# MKRWAN1310V3_0.net
KiCad netlist of a schematic drawn in EAGLE
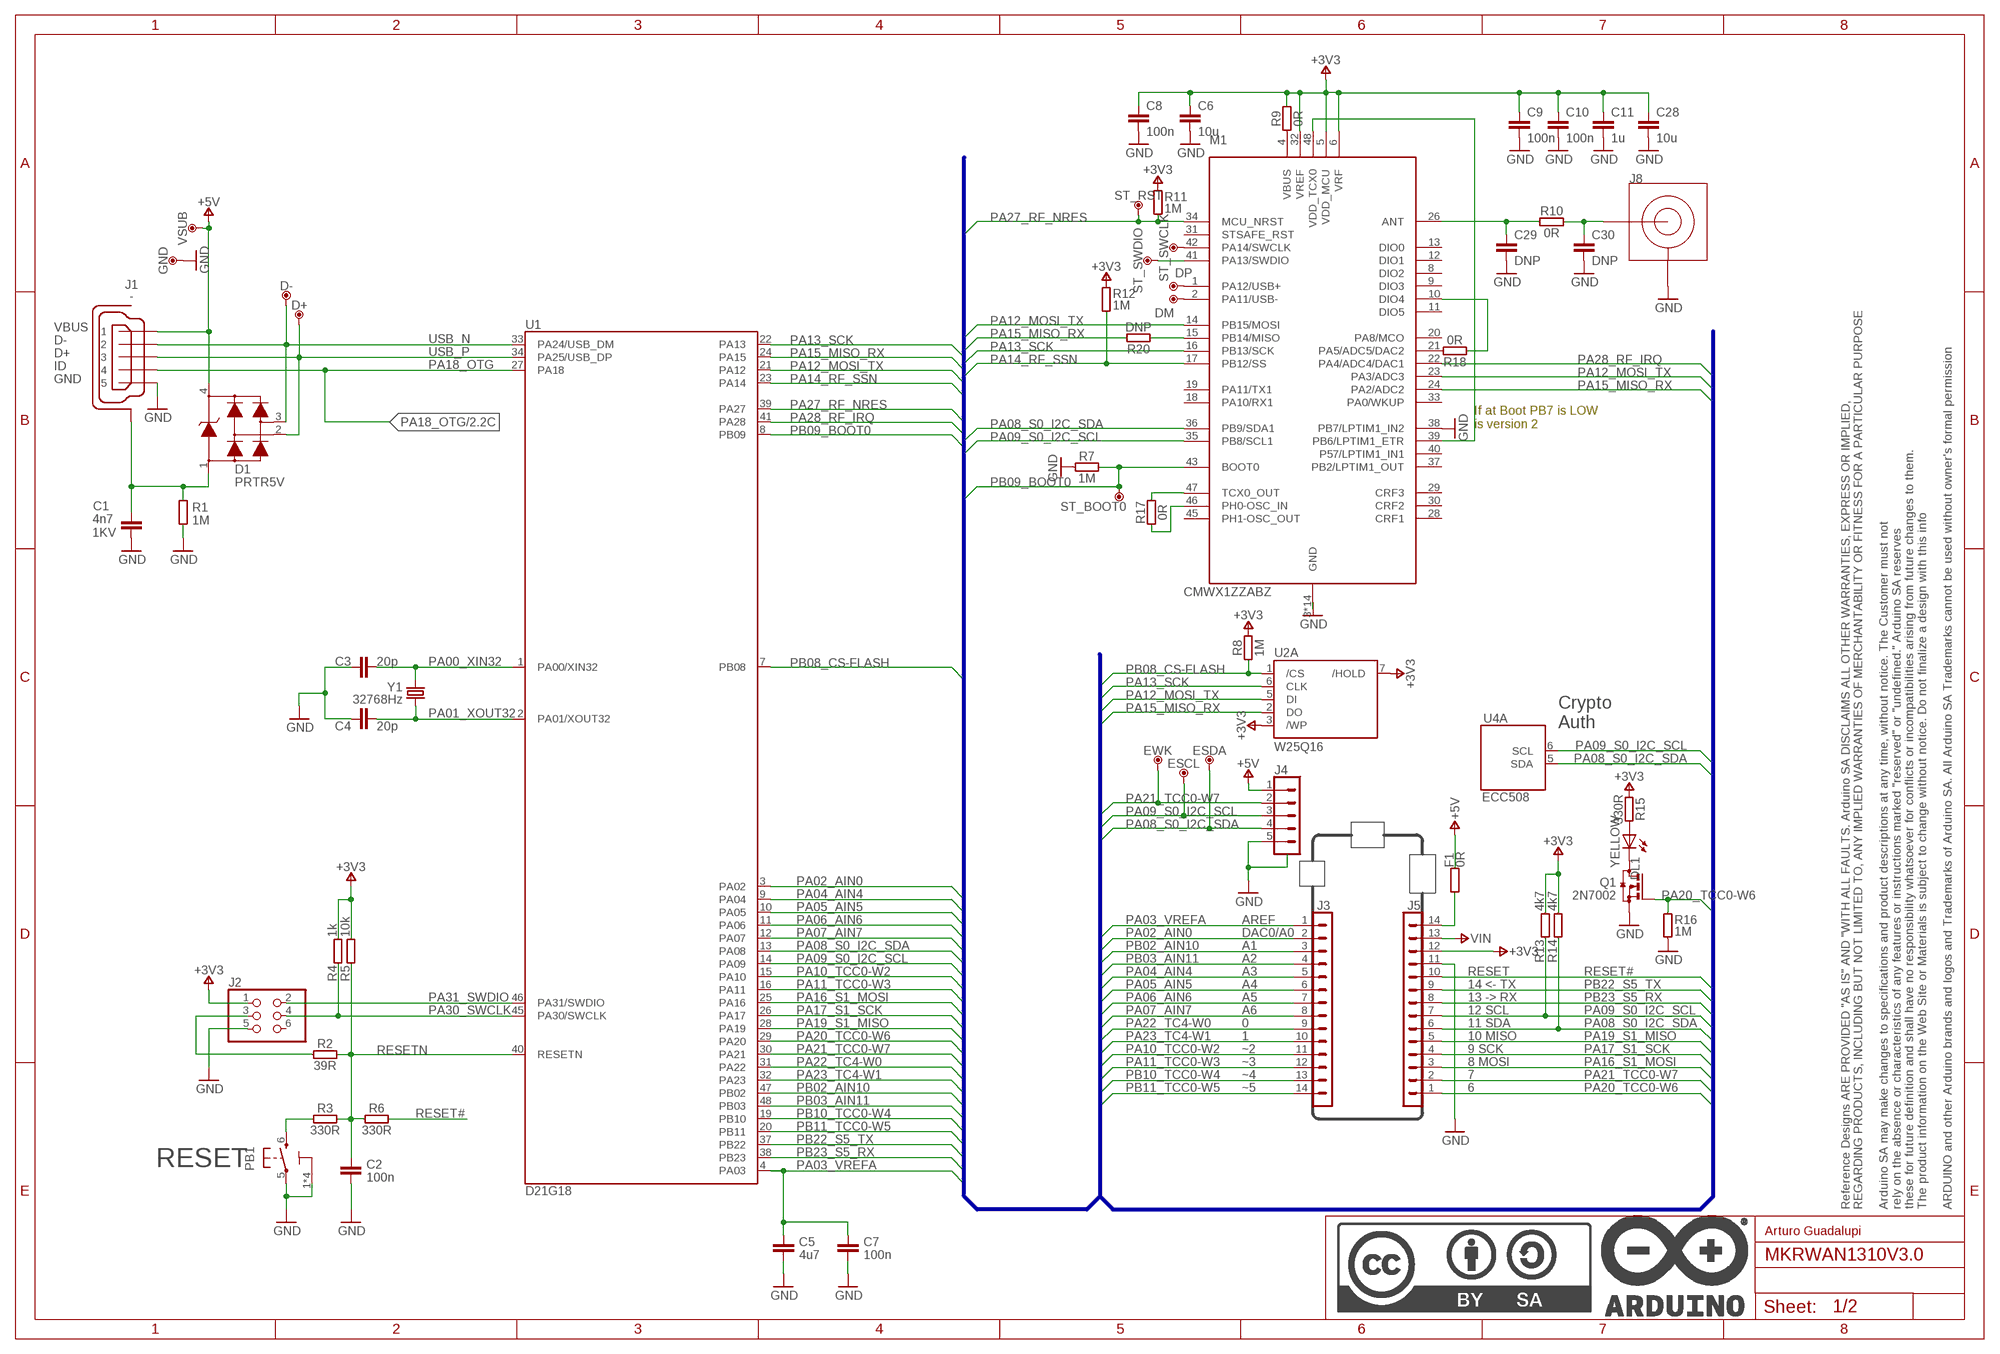
[diagram p0: schematic, sheet 1]
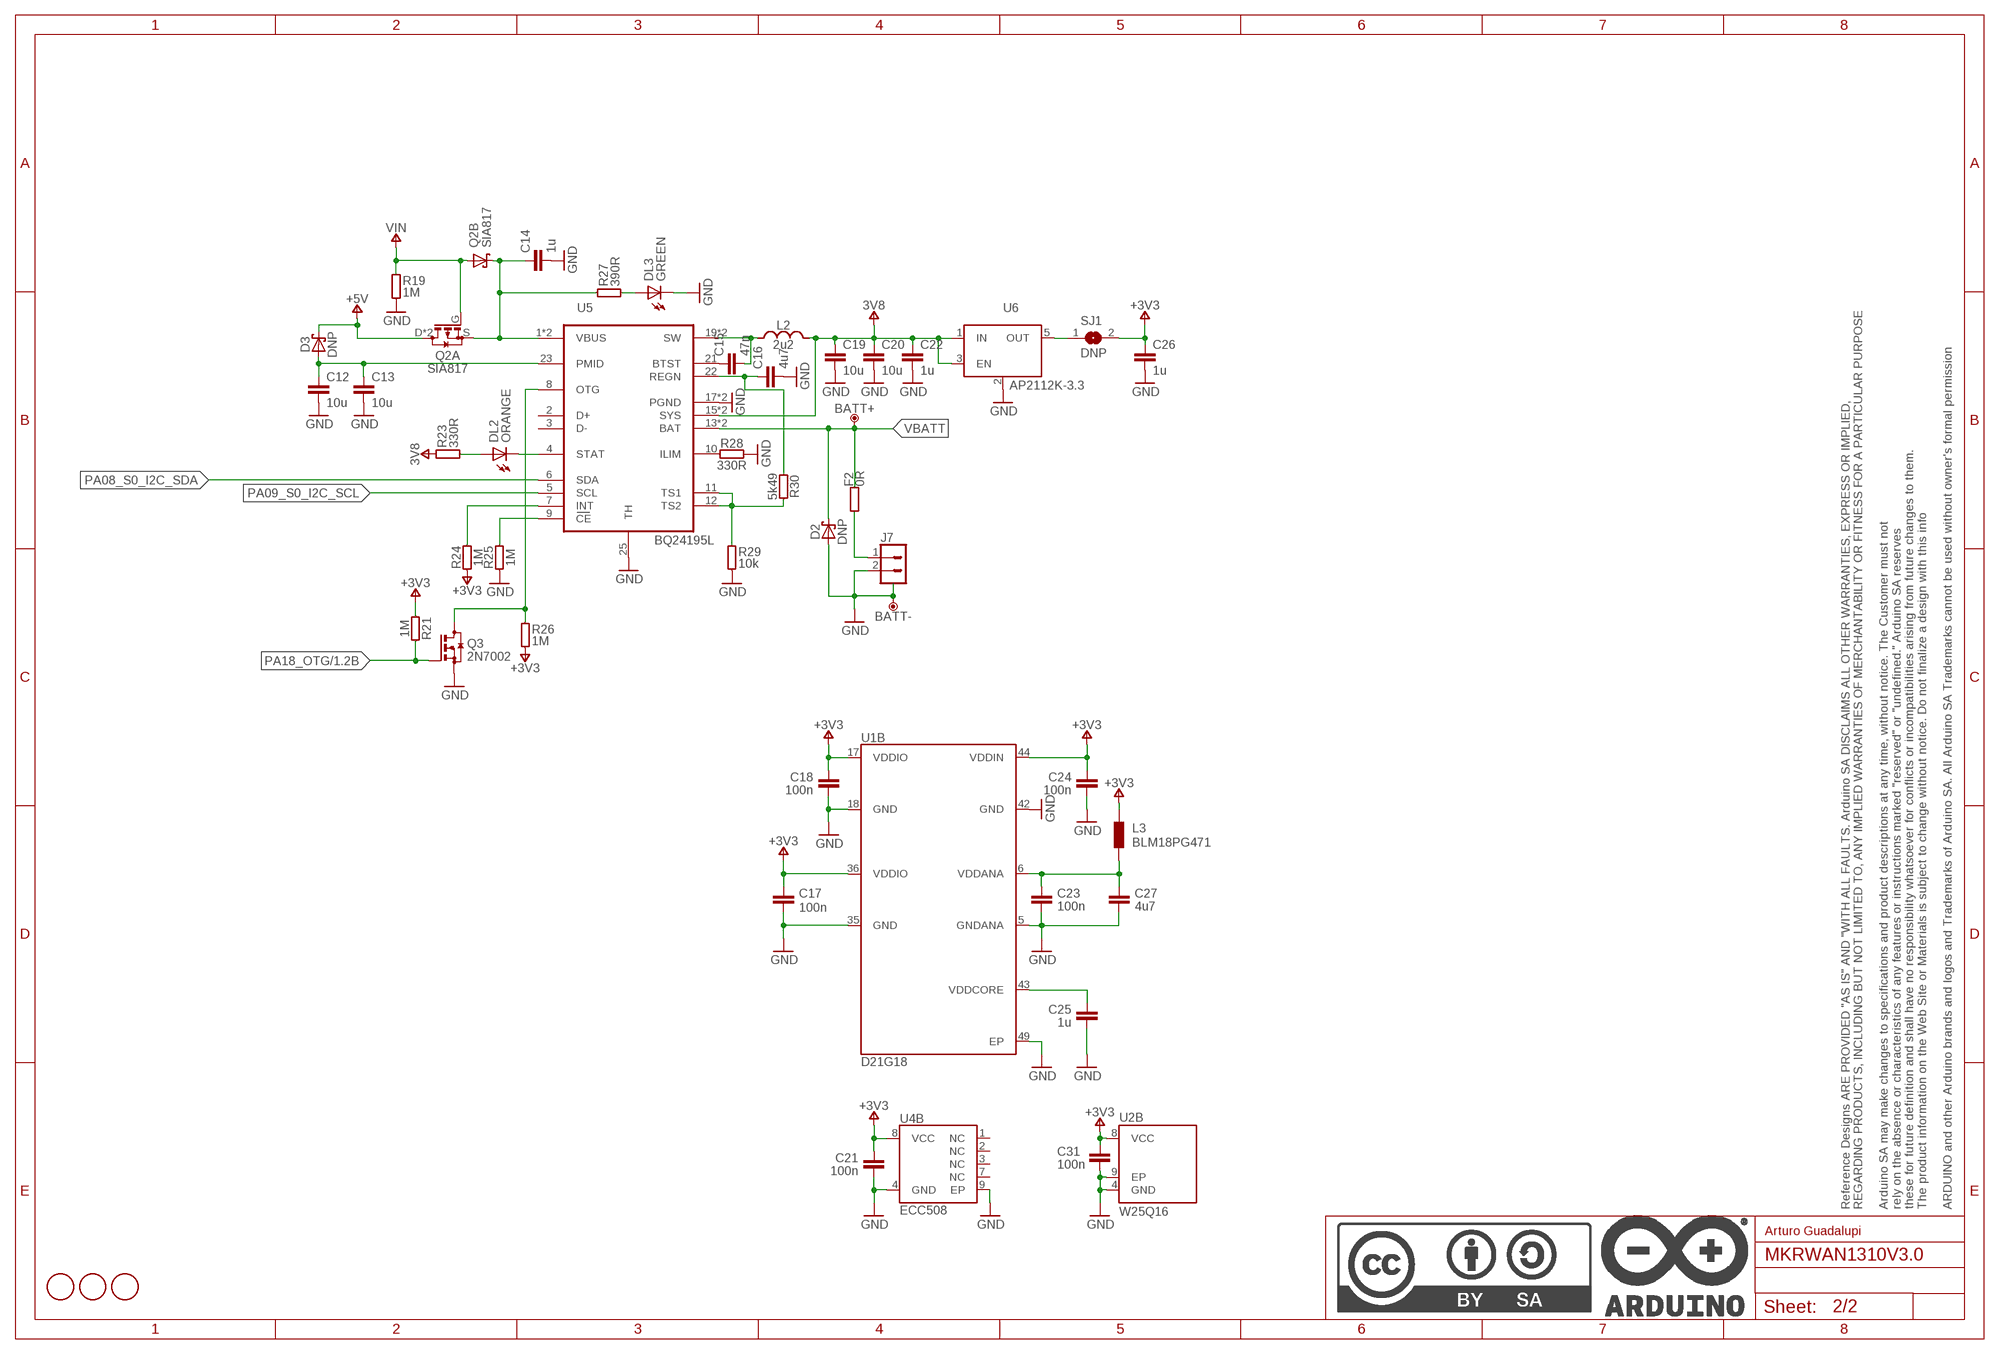
[diagram p1: schematic, sheet 2]

(export (version "E")
  (design (tool "Eeschema 10.0.6"))
  (components
    (comp (ref "C1")
      (value "4n7")
      (footprint "eagle-import:0805-R2013X50N")
      (fields (field (name "MANUFACTURER") "Kemet") (field (name "VOLTAGE") "1KV"))
      (libsource (lib "eagle-import") (part "C-08054.7NF"))
    )
    (comp (ref "C2")
      (value "100n")
      (footprint "eagle-import:0402-1005X55N")
      (fields (field (name "MANUFACTURER") "TDK"))
      (libsource (lib "eagle-import") (part "C-0402-100NF"))
    )
    (comp (ref "C3")
      (value "20p")
      (footprint "eagle-import:0402-1005X55N")
      (fields (field (name "MANUFACTURER") "Kemet"))
      (libsource (lib "eagle-import") (part "C-0402-20PF"))
    )
    (comp (ref "C4")
      (value "20p")
      (footprint "eagle-import:0402-1005X55N")
      (fields (field (name "MANUFACTURER") "Kemet"))
      (libsource (lib "eagle-import") (part "C-0402-20PF"))
    )
    (comp (ref "C5")
      (value "4u7")
      (footprint "eagle-import:0402-1005X55N")
      (fields (field (name "MANUFACTURER") "Murata"))
      (libsource (lib "eagle-import") (part "C-0402-4.7UF"))
    )
    (comp (ref "C6")
      (value "10u")
      (footprint "eagle-import:0603-1608X90N")
      (fields (field (name "MANUFACTURER") "Murata"))
      (libsource (lib "eagle-import") (part "C-0603-10UF"))
    )
    (comp (ref "C7")
      (value "100n")
      (footprint "eagle-import:0402-1005X55N")
      (fields (field (name "MANUFACTURER") "TDK"))
      (libsource (lib "eagle-import") (part "C-0402-100NF"))
    )
    (comp (ref "C8")
      (value "100n")
      (footprint "eagle-import:0402-1005X55N")
      (fields (field (name "MANUFACTURER") "TDK"))
      (libsource (lib "eagle-import") (part "C-0402-100NF"))
    )
    (comp (ref "C9")
      (value "100n")
      (footprint "eagle-import:0402-1005X55N")
      (fields (field (name "MANUFACTURER") "TDK"))
      (libsource (lib "eagle-import") (part "C-0402-100NF"))
    )
    (comp (ref "C10")
      (value "100n")
      (footprint "eagle-import:0402-1005X55N")
      (fields (field (name "MANUFACTURER") "TDK"))
      (libsource (lib "eagle-import") (part "C-0402-100NF"))
    )
    (comp (ref "C11")
      (value "1u")
      (footprint "eagle-import:0402-1005X55N")
      (fields (field (name "MANUFACTURER") "Murata"))
      (libsource (lib "eagle-import") (part "C-0402-1UF"))
    )
    (comp (ref "C28")
      (value "10u")
      (footprint "eagle-import:0603-1608X90N")
      (fields (field (name "MANUFACTURER") "Murata"))
      (libsource (lib "eagle-import") (part "C-0603-10UF"))
    )
    (comp (ref "C29")
      (value "DNP")
      (footprint "eagle-import:0402-1005X55N")
      (libsource (lib "eagle-import") (part "C-0402DNP"))
    )
    (comp (ref "C30")
      (value "DNP")
      (footprint "eagle-import:0402-1005X55N")
      (libsource (lib "eagle-import") (part "C-0402DNP"))
    )
    (comp (ref "D+")
      (value "DNP")
      (footprint "eagle-import:TP-1.00MM")
      (libsource (lib "eagle-import") (part "TPTP-1.00MM"))
    )
    (comp (ref "D-")
      (value "DNP")
      (footprint "eagle-import:TP-1.00MM")
      (libsource (lib "eagle-import") (part "TPTP-1.00MM"))
    )
    (comp (ref "D1")
      (value "PRTR5V")
      (footprint "eagle-import:SOT190P230X110-4N")
      (fields (field (name "MANUFACTURER") "NXP"))
      (libsource (lib "eagle-import") (part "PRTR5V0U2X,215"))
    )
    (comp (ref "DL1")
      (value "YELLOW")
      (footprint "eagle-import:LEDC1608X80N-AK")
      (fields (field (name "MANUFACTURER") "Avago"))
      (libsource (lib "eagle-import") (part "LED-0603-YELLOW"))
    )
    (comp (ref "DM")
      (value "DNP")
      (footprint "eagle-import:TP-1.27MM")
      (libsource (lib "eagle-import") (part "TPTP-1.27MM"))
    )
    (comp (ref "DP")
      (value "DNP")
      (footprint "eagle-import:TP-1.27MM")
      (libsource (lib "eagle-import") (part "TPTP-1.27MM"))
    )
    (comp (ref "ESCL")
      (value "DNP")
      (footprint "eagle-import:TP-1.00MM")
      (libsource (lib "eagle-import") (part "TPTP-1.00MM"))
    )
    (comp (ref "ESDA")
      (value "DNP")
      (footprint "eagle-import:TP-1.00MM")
      (libsource (lib "eagle-import") (part "TPTP-1.00MM"))
    )
    (comp (ref "EWK")
      (value "DNP")
      (footprint "eagle-import:TP-1.00MM")
      (libsource (lib "eagle-import") (part "TPTP-1.00MM"))
    )
    (comp (ref "F1")
      (value "0R")
      (footprint "eagle-import:C0603")
      (fields (field (name "MANUFACTURER") "Yageo"))
      (libsource (lib "eagle-import") (part "R-0603-0R"))
    )
    (comp (ref "FRAME1")
      (value "DNP")
      (footprint "eagle-import:FRAME")
      (libsource (lib "eagle-import") (part "A3-FRAME"))
    )
    (comp (ref "GND")
      (value "DNP")
      (footprint "eagle-import:TP-1.00MM")
      (libsource (lib "eagle-import") (part "TPTP-1.00MM"))
    )
    (comp (ref "J1")
      (value "-")
      (footprint "eagle-import:ZX62-AB-5PA")
      (fields (field (name "MANUFACTURER") "Hirose"))
      (libsource (lib "eagle-import") (part "USB-MICRO"))
    )
    (comp (ref "J2")
      (value "DNP")
      (footprint "eagle-import:2X3_SMT")
      (libsource (lib "eagle-import") (part "PINHD-2X03SMD-NH-DNP"))
    )
    (comp (ref "J3")
      (value "-")
      (footprint "eagle-import:1X14_SMD_TH")
      (fields (field (name "MANUFACTURER") "ELDECO"))
      (libsource (lib "eagle-import") (part "PINHD-1X14-SMTH-SMD-MALE/FEMALE"))
    )
    (comp (ref "J4")
      (value "-")
      (footprint "eagle-import:SM05B-SRSS-TB")
      (fields (field (name "MANUFACTURER") "JST"))
      (libsource (lib "eagle-import") (part "SM05B-SRSS-TB"))
    )
    (comp (ref "J5")
      (value "-")
      (footprint "eagle-import:1X14_SMD_TH")
      (fields (field (name "MANUFACTURER") "ELDECO"))
      (libsource (lib "eagle-import") (part "PINHD-1X14-SMTH-SMD-MALE/FEMALE"))
    )
    (comp (ref "J8")
      (value "-")
      (footprint "eagle-import:U.FL-R-SMT-1(60)")
      (fields (field (name "MANUFACTURER") "Hirose"))
      (libsource (lib "eagle-import") (part "UFL"))
    )
    (comp (ref "M1")
      (value "CMWX1ZZABZ")
      (footprint "eagle-import:CMWX1ZZABZ")
      (fields (field (name "MANUFACTURER") "Murata"))
      (libsource (lib "eagle-import") (part "CMWX1ZZABZ"))
    )
    (comp (ref "PB1")
      (value "PTS820")
      (footprint "eagle-import:C&K_PTS820_NO_HOLES")
      (fields (field (name "MANUFACTURER") "C&K"))
      (libsource (lib "eagle-import") (part "TACTILE1PTS820-NH"))
    )
    (comp (ref "Q1")
      (value "2N7002")
      (footprint "eagle-import:SOTFL50P160X78-3")
      (fields (field (name "MANUFACTURER") "Diodes Incorporated"))
      (libsource (lib "eagle-import") (part "2N7002T-SOT523"))
    )
    (comp (ref "R1")
      (value "1M")
      (footprint "eagle-import:0402-1005X55N")
      (fields (field (name "MANUFACTURER") "Yageo"))
      (libsource (lib "eagle-import") (part "R-0402-1M"))
    )
    (comp (ref "R2")
      (value "39R")
      (footprint "eagle-import:0402-1005X55N")
      (fields (field (name "MANUFACTURER") "Yageo "))
      (libsource (lib "eagle-import") (part "R-0402-39R"))
    )
    (comp (ref "R3")
      (value "330R")
      (footprint "eagle-import:0402-1005X55N")
      (fields (field (name "MANUFACTURER") "Yageo "))
      (libsource (lib "eagle-import") (part "R-0402-330R"))
    )
    (comp (ref "R4")
      (value "1k")
      (footprint "eagle-import:0402-1005X55N")
      (fields (field (name "MANUFACTURER") "Yageo"))
      (libsource (lib "eagle-import") (part "R-0402-1K"))
    )
    (comp (ref "R5")
      (value "10k")
      (footprint "eagle-import:0402-1005X55N")
      (fields (field (name "MANUFACTURER") "Yageo"))
      (libsource (lib "eagle-import") (part "R-0402-10K"))
    )
    (comp (ref "R6")
      (value "330R")
      (footprint "eagle-import:0402-1005X55N")
      (fields (field (name "MANUFACTURER") "Yageo "))
      (libsource (lib "eagle-import") (part "R-0402-330R"))
    )
    (comp (ref "R7")
      (value "1M")
      (footprint "eagle-import:0402-1005X55N")
      (fields (field (name "MANUFACTURER") "Yageo"))
      (libsource (lib "eagle-import") (part "R-0402-1M"))
    )
    (comp (ref "R8")
      (value "1M")
      (footprint "eagle-import:0402-1005X55N")
      (fields (field (name "MANUFACTURER") "Yageo"))
      (libsource (lib "eagle-import") (part "R-0402-1M"))
    )
    (comp (ref "R9")
      (value "0R")
      (footprint "eagle-import:0402-1005X55N")
      (fields (field (name "MANUFACTURER") "Yageo"))
      (libsource (lib "eagle-import") (part "R-0402-0R"))
    )
    (comp (ref "R10")
      (value "0R")
      (footprint "eagle-import:0402-1005X55N")
      (fields (field (name "MANUFACTURER") "Yageo"))
      (libsource (lib "eagle-import") (part "R-0402-0R"))
    )
    (comp (ref "R11")
      (value "1M")
      (footprint "eagle-import:0402-1005X55N")
      (fields (field (name "MANUFACTURER") "Yageo"))
      (libsource (lib "eagle-import") (part "R-0402-1M"))
    )
    (comp (ref "R12")
      (value "1M")
      (footprint "eagle-import:0402-1005X55N")
      (fields (field (name "MANUFACTURER") "Yageo"))
      (libsource (lib "eagle-import") (part "R-0402-1M"))
    )
    (comp (ref "R13")
      (value "4k7")
      (footprint "eagle-import:0402-1005X55N")
      (fields (field (name "MANUFACTURER") "Yageo "))
      (libsource (lib "eagle-import") (part "R-0402-4K7"))
    )
    (comp (ref "R14")
      (value "4k7")
      (footprint "eagle-import:0402-1005X55N")
      (fields (field (name "MANUFACTURER") "Yageo "))
      (libsource (lib "eagle-import") (part "R-0402-4K7"))
    )
    (comp (ref "R15")
      (value "330R")
      (footprint "eagle-import:0402-1005X55N")
      (fields (field (name "MANUFACTURER") "Yageo "))
      (libsource (lib "eagle-import") (part "R-0402-330R"))
    )
    (comp (ref "R16")
      (value "1M")
      (footprint "eagle-import:0402-1005X55N")
      (fields (field (name "MANUFACTURER") "Yageo"))
      (libsource (lib "eagle-import") (part "R-0402-1M"))
    )
    (comp (ref "R17")
      (value "0R")
      (footprint "eagle-import:0402-1005X55N")
      (fields (field (name "MANUFACTURER") "Yageo"))
      (libsource (lib "eagle-import") (part "R-0402-0R"))
    )
    (comp (ref "R18")
      (value "0R")
      (footprint "eagle-import:0402-1005X55N")
      (fields (field (name "MANUFACTURER") "Yageo"))
      (libsource (lib "eagle-import") (part "R-0402-0R"))
    )
    (comp (ref "R20")
      (value "DNP")
      (footprint "eagle-import:0402-1005X55N")
      (libsource (lib "eagle-import") (part "R-0402-DNP"))
    )
    (comp (ref "ST_BOOT0")
      (value "DNP")
      (footprint "eagle-import:TP-0.8MM")
      (libsource (lib "eagle-import") (part "TPTP-0.8MM"))
    )
    (comp (ref "ST_RST")
      (value "DNP")
      (footprint "eagle-import:TP-0.8MM")
      (libsource (lib "eagle-import") (part "TPTP-0.8MM"))
    )
    (comp (ref "ST_SWCLK")
      (value "DNP")
      (footprint "eagle-import:TP-0.8MM")
      (libsource (lib "eagle-import") (part "TPTP-0.8MM"))
    )
    (comp (ref "ST_SWDIO")
      (value "DNP")
      (footprint "eagle-import:TP-0.8MM")
      (libsource (lib "eagle-import") (part "TPTP-0.8MM"))
    )
    (comp (ref "U1")
      (value "D21G18")
      (footprint "eagle-import:QFN50P700X700X90-49XN-EPSQ515")
      (fields (field (name "MANUFACTURER") "Atmel"))
      (libsource (lib "eagle-import") (part "ATSAMD21G18A-48QFN"))
    )
    (comp (ref "U2")
      (value "W25Q16")
      (footprint "eagle-import:SON9P127_500X600X80L60X41T340X400N")
      (fields (field (name "MANUFACTURER") "Winbond"))
      (libsource (lib "eagle-import") (part "W25QZP16DV?IG"))
    )
    (comp (ref "U4")
      (value "ECC508")
      (footprint "eagle-import:SON50P300X200X60-9N-EP160X140")
      (fields (field (name "MANUFACTURER") "Atmel"))
      (libsource (lib "eagle-import") (part "ATECC508A-MAHDA-T8-UDFN"))
    )
    (comp (ref "VSUB")
      (value "DNP")
      (footprint "eagle-import:TP-1.00MM")
      (libsource (lib "eagle-import") (part "TPTP-1.00MM"))
    )
    (comp (ref "Y1")
      (value "32768Hz")
      (footprint "eagle-import:ABS07")
      (fields (field (name "MANUFACTURER") "Abracon LLC"))
      (libsource (lib "eagle-import") (part "32.768KHZ"))
    )
    (comp (ref "BATT+")
      (value "DNP")
      (footprint "eagle-import:TP-1.00MM")
      (libsource (lib "eagle-import") (part "TPTP-1.00MM"))
    )
    (comp (ref "BATT-")
      (value "DNP")
      (footprint "eagle-import:TP-1.00MM")
      (libsource (lib "eagle-import") (part "TPTP-1.00MM"))
    )
    (comp (ref "C12")
      (value "10u")
      (footprint "eagle-import:0603-1608X90N")
      (fields (field (name "MANUFACTURER") "Murata"))
      (libsource (lib "eagle-import") (part "C-0603-10UF"))
    )
    (comp (ref "C13")
      (value "10u")
      (footprint "eagle-import:0603-1608X90N")
      (fields (field (name "MANUFACTURER") "Murata"))
      (libsource (lib "eagle-import") (part "C-0603-10UF"))
    )
    (comp (ref "C14")
      (value "1u")
      (footprint "eagle-import:0402-1005X55N")
      (fields (field (name "MANUFACTURER") "Murata"))
      (libsource (lib "eagle-import") (part "C-0402-1UF"))
    )
    (comp (ref "C15")
      (value "47n")
      (footprint "eagle-import:0402-1005X55N")
      (fields (field (name "MANUFACTURER") "Murata"))
      (libsource (lib "eagle-import") (part "C-0402-47N"))
    )
    (comp (ref "C16")
      (value "4u7")
      (footprint "eagle-import:0402-1005X55N")
      (fields (field (name "MANUFACTURER") "Murata"))
      (libsource (lib "eagle-import") (part "C-0402-4.7UF"))
    )
    (comp (ref "C17")
      (value "100n")
      (footprint "eagle-import:0402-1005X55N")
      (fields (field (name "MANUFACTURER") "TDK"))
      (libsource (lib "eagle-import") (part "C-0402-100NF"))
    )
    (comp (ref "C18")
      (value "100n")
      (footprint "eagle-import:0402-1005X55N")
      (fields (field (name "MANUFACTURER") "TDK"))
      (libsource (lib "eagle-import") (part "C-0402-100NF"))
    )
    (comp (ref "C19")
      (value "10u")
      (footprint "eagle-import:0603-1608X90N")
      (fields (field (name "MANUFACTURER") "Murata"))
      (libsource (lib "eagle-import") (part "C-0603-10UF"))
    )
    (comp (ref "C20")
      (value "10u")
      (footprint "eagle-import:0603-1608X90N")
      (fields (field (name "MANUFACTURER") "Murata"))
      (libsource (lib "eagle-import") (part "C-0603-10UF"))
    )
    (comp (ref "C21")
      (value "100n")
      (footprint "eagle-import:0402-1005X55N")
      (fields (field (name "MANUFACTURER") "TDK"))
      (libsource (lib "eagle-import") (part "C-0402-100NF"))
    )
    (comp (ref "C22")
      (value "1u")
      (footprint "eagle-import:0402-1005X55N")
      (fields (field (name "MANUFACTURER") "Murata"))
      (libsource (lib "eagle-import") (part "C-0402-1UF"))
    )
    (comp (ref "C23")
      (value "100n")
      (footprint "eagle-import:0402-1005X55N")
      (fields (field (name "MANUFACTURER") "TDK"))
      (libsource (lib "eagle-import") (part "C-0402-100NF"))
    )
    (comp (ref "C24")
      (value "100n")
      (footprint "eagle-import:0402-1005X55N")
      (fields (field (name "MANUFACTURER") "TDK"))
      (libsource (lib "eagle-import") (part "C-0402-100NF"))
    )
    (comp (ref "C25")
      (value "1u")
      (footprint "eagle-import:0402-1005X55N")
      (fields (field (name "MANUFACTURER") "Murata"))
      (libsource (lib "eagle-import") (part "C-0402-1UF"))
    )
    (comp (ref "C26")
      (value "1u")
      (footprint "eagle-import:0402-1005X55N")
      (fields (field (name "MANUFACTURER") "Murata"))
      (libsource (lib "eagle-import") (part "C-0402-1UF"))
    )
    (comp (ref "C27")
      (value "4u7")
      (footprint "eagle-import:0603-1608X90N")
      (fields (field (name "MANUFACTURER") "Murata"))
      (libsource (lib "eagle-import") (part "C-0603-4.7UF"))
    )
    (comp (ref "C31")
      (value "100n")
      (footprint "eagle-import:0402-1005X55N")
      (fields (field (name "MANUFACTURER") "TDK"))
      (libsource (lib "eagle-import") (part "C-0402-100NF"))
    )
    (comp (ref "D2")
      (value "DNP")
      (footprint "eagle-import:SODFL3517X110N")
      (libsource (lib "eagle-import") (part "PMEG6020AELRX-DNP"))
    )
    (comp (ref "D3")
      (value "DNP")
      (footprint "eagle-import:SODFL3517X110N")
      (libsource (lib "eagle-import") (part "PMEG6020AELRX-DNP"))
    )
    (comp (ref "DL2")
      (value "ORANGE")
      (footprint "eagle-import:LEDC1608X80N-AK")
      (fields (field (name "MANUFACTURER") "Avago "))
      (libsource (lib "eagle-import") (part "LED-0603-ORANGE"))
    )
    (comp (ref "DL3")
      (value "GREEN")
      (footprint "eagle-import:LEDC1608X80N-AK")
      (fields (field (name "MANUFACTURER") "Avago "))
      (libsource (lib "eagle-import") (part "LED-0603-GREEN"))
    )
    (comp (ref "F2")
      (value "0R")
      (footprint "eagle-import:C0603")
      (fields (field (name "MANUFACTURER") "Yageo"))
      (libsource (lib "eagle-import") (part "R-0603-0R"))
    )
    (comp (ref "FD1")
      (value "DNP")
      (footprint "eagle-import:FD-1-1.5")
      (libsource (lib "eagle-import") (part "FIDUCIAL-1.5MM"))
    )
    (comp (ref "FD2")
      (value "DNP")
      (footprint "eagle-import:FD-1-1.5")
      (libsource (lib "eagle-import") (part "FIDUCIAL-1.5MM"))
    )
    (comp (ref "FD3")
      (value "DNP")
      (footprint "eagle-import:FD-1-1.5")
      (libsource (lib "eagle-import") (part "FIDUCIAL-1.5MM"))
    )
    (comp (ref "FRAME2")
      (value "DNP")
      (footprint "eagle-import:FRAME")
      (libsource (lib "eagle-import") (part "A3-FRAME"))
    )
    (comp (ref "J7")
      (value "-")
      (footprint "eagle-import:JST-S2B-PH-SM4-TB")
      (fields (field (name "MANUFACTURER") "JST "))
      (libsource (lib "eagle-import") (part "BATTERY"))
    )
    (comp (ref "L2")
      (value "2u2")
      (footprint "eagle-import:SRP4020")
      (fields (field (name "MANUFACTURER") "Bourns"))
      (libsource (lib "eagle-import") (part "LSRP"))
    )
    (comp (ref "L3")
      (value "BLM18PG471")
      (footprint "eagle-import:0603-1608X90N")
      (fields (field (name "MANUFACTURER") "Murata"))
      (libsource (lib "eagle-import") (part "FERRITE0603-470R"))
    )
    (comp (ref "Q2")
      (value "SIA817")
      (footprint "eagle-import:SON65P205X205X75-8N-MWSD")
      (fields (field (name "MANUFACTURER") "Vishay "))
      (libsource (lib "eagle-import") (part "SIA817EDJ"))
    )
    (comp (ref "Q3")
      (value "2N7002")
      (footprint "eagle-import:SOTFL50P160X78-3")
      (fields (field (name "MANUFACTURER") "Diodes Incorporated"))
      (libsource (lib "eagle-import") (part "2N7002T-SOT523"))
    )
    (comp (ref "R19")
      (value "1M")
      (footprint "eagle-import:0402-1005X55N")
      (fields (field (name "MANUFACTURER") "Yageo"))
      (libsource (lib "eagle-import") (part "R-0402-1M"))
    )
    (comp (ref "R21")
      (value "1M")
      (footprint "eagle-import:0402-1005X55N")
      (fields (field (name "MANUFACTURER") "Yageo"))
      (libsource (lib "eagle-import") (part "R-0402-1M"))
    )
    (comp (ref "R23")
      (value "330R")
      (footprint "eagle-import:0402-1005X55N")
      (fields (field (name "MANUFACTURER") "Yageo "))
      (libsource (lib "eagle-import") (part "R-0402-330R"))
    )
    (comp (ref "R24")
      (value "1M")
      (footprint "eagle-import:0402-1005X55N")
      (fields (field (name "MANUFACTURER") "Yageo"))
      (libsource (lib "eagle-import") (part "R-0402-1M"))
    )
    (comp (ref "R25")
      (value "1M")
      (footprint "eagle-import:0402-1005X55N")
      (fields (field (name "MANUFACTURER") "Yageo"))
      (libsource (lib "eagle-import") (part "R-0402-1M"))
    )
    (comp (ref "R26")
      (value "1M")
      (footprint "eagle-import:0402-1005X55N")
      (fields (field (name "MANUFACTURER") "Yageo"))
      (libsource (lib "eagle-import") (part "R-0402-1M"))
    )
    (comp (ref "R27")
      (value "390R")
      (footprint "eagle-import:0402-1005X55N")
      (fields (field (name "MANUFACTURER") "Yageo"))
      (libsource (lib "eagle-import") (part "R-0402-390R"))
    )
    (comp (ref "R28")
      (value "330R")
      (footprint "eagle-import:0402-1005X55N")
      (fields (field (name "MANUFACTURER") "Yageo "))
      (libsource (lib "eagle-import") (part "R-0402-330R"))
    )
    (comp (ref "R29")
      (value "10k")
      (footprint "eagle-import:0402-1005X55N")
      (fields (field (name "MANUFACTURER") "Yageo"))
      (libsource (lib "eagle-import") (part "R-0402-10K"))
    )
    (comp (ref "R30")
      (value "5k49")
      (footprint "eagle-import:0402-1005X55N")
      (fields (field (name "MANUFACTURER") "Yageo"))
      (libsource (lib "eagle-import") (part "R-0402-5K49"))
    )
    (comp (ref "SJ1")
      (value "DNP")
      (footprint "eagle-import:SJ")
      (libsource (lib "eagle-import") (part "SJ"))
    )
    (comp (ref "U5")
      (value "BQ24195L")
      (footprint "eagle-import:QFN24")
      (fields (field (name "MANUFACTURER") " Texas Instruments "))
      (libsource (lib "eagle-import") (part "BQ24195QFN-24"))
    )
    (comp (ref "U6")
      (value "AP2112K-3.3")
      (footprint "eagle-import:SOT25")
      (fields (field (name "MANUFACTURER") "Diodes Inc"))
      (libsource (lib "eagle-import") (part "AP2112K-3.3"))
    )
  )
  (nets
    (net (code "1") (name "+3V3") (class "Default")
      (node (ref "C10") (pin "1") (pinfunction "1_1") (pintype "passive"))
      (node (ref "C11") (pin "1") (pinfunction "1_1") (pintype "passive"))
      (node (ref "C17") (pin "1") (pinfunction "1_1") (pintype "passive"))
      (node (ref "C18") (pin "1") (pinfunction "1_1") (pintype "passive"))
      (node (ref "C21") (pin "1") (pinfunction "1_1") (pintype "passive"))
      (node (ref "C24") (pin "1") (pinfunction "1_1") (pintype "passive"))
      (node (ref "C26") (pin "1") (pinfunction "1_1") (pintype "passive"))
      (node (ref "C28") (pin "1") (pinfunction "1_1") (pintype "passive"))
      (node (ref "C31") (pin "2") (pinfunction "2_2") (pintype "passive"))
      (node (ref "C6") (pin "1") (pinfunction "1_1") (pintype "passive"))
      (node (ref "C8") (pin "1") (pinfunction "1_1") (pintype "passive"))
      (node (ref "C9") (pin "1") (pinfunction "1_1") (pintype "passive"))
      (node (ref "J2") (pin "1") (pinfunction "1_1") (pintype "passive"))
      (node (ref "J5") (pin "12") (pinfunction "12_12") (pintype "passive"))
      (node (ref "L3") (pin "1") (pinfunction "1_1") (pintype "passive"))
      (node (ref "M1") (pin "32") (pinfunction "VREF_32") (pintype "bidirectional"))
      (node (ref "M1") (pin "5") (pinfunction "VDD_MCU_5") (pintype "bidirectional"))
      (node (ref "M1") (pin "6") (pinfunction "VRF_6") (pintype "bidirectional"))
      (node (ref "R11") (pin "2") (pinfunction "2_2") (pintype "passive"))
      (node (ref "R12") (pin "2") (pinfunction "2_2") (pintype "passive"))
      (node (ref "R13") (pin "2") (pinfunction "2_2") (pintype "passive"))
      (node (ref "R14") (pin "2") (pinfunction "2_2") (pintype "passive"))
      (node (ref "R15") (pin "1") (pinfunction "1_1") (pintype "passive"))
      (node (ref "R21") (pin "1") (pinfunction "1_1") (pintype "passive"))
      (node (ref "R24") (pin "1") (pinfunction "1_1") (pintype "passive"))
      (node (ref "R26") (pin "1") (pinfunction "1_1") (pintype "passive"))
      (node (ref "R4") (pin "2") (pinfunction "2_2") (pintype "passive"))
      (node (ref "R5") (pin "2") (pinfunction "2_2") (pintype "passive"))
      (node (ref "R8") (pin "2") (pinfunction "2_2") (pintype "passive"))
      (node (ref "R9") (pin "2") (pinfunction "2_2") (pintype "passive"))
      (node (ref "SJ1") (pin "2") (pinfunction "2_2") (pintype "passive"))
      (node (ref "U1") (pin "17") (pinfunction "VDDIO_17") (pintype "power_in"))
      (node (ref "U1") (pin "36") (pinfunction "VDDIO_36") (pintype "power_in"))
      (node (ref "U1") (pin "44") (pinfunction "VDDIN_44") (pintype "power_in"))
      (node (ref "U2") (pin "3") (pinfunction "/WP_3") (pintype "input"))
      (node (ref "U2") (pin "7") (pinfunction "/HOLD_7") (pintype "input"))
      (node (ref "U2") (pin "8") (pinfunction "VCC_8") (pintype "power_in"))
      (node (ref "U4") (pin "8") (pinfunction "VCC_8") (pintype "power_in"))
    )
    (net (code "2") (name "+3V8") (class "Default")
      (node (ref "C19") (pin "1") (pinfunction "1_1") (pintype "passive"))
      (node (ref "C20") (pin "1") (pinfunction "1_1") (pintype "passive"))
      (node (ref "C22") (pin "1") (pinfunction "1_1") (pintype "passive"))
      (node (ref "L2") (pin "2") (pinfunction "2_2") (pintype "passive"))
      (node (ref "R23") (pin "2") (pinfunction "2_2") (pintype "passive"))
      (node (ref "U5") (pin "15") (pinfunction "SYS_15") (pintype "bidirectional"))
      (node (ref "U5") (pin "16") (pinfunction "SYS_16") (pintype "bidirectional"))
      (node (ref "U6") (pin "1") (pinfunction "IN_1") (pintype "power_in"))
      (node (ref "U6") (pin "3") (pinfunction "EN_3") (pintype "input"))
    )
    (net (code "3") (name "+5V") (class "Default")
      (node (ref "D1") (pin "4") (pinfunction "4_4") (pintype "passive"))
      (node (ref "D3") (pin "C") (pinfunction "C_C") (pintype "passive"))
      (node (ref "F1") (pin "2") (pinfunction "2_2") (pintype "passive"))
      (node (ref "J1") (pin "1") (pinfunction "1_1") (pintype "passive"))
      (node (ref "J4") (pin "1") (pinfunction "1_1") (pintype "passive"))
      (node (ref "Q2") (pin "D") (pinfunction "D_D") (pintype "passive"))
      (node (ref "Q2") (pin "D2") (pinfunction "D_D2") (pintype "passive"))
      (node (ref "VSUB") (pin "X") (pinfunction "P$1_X") (pintype "passive"))
    )
    (net (code "4") (name "GND") (class "Default")
      (node (ref "BATT-") (pin "X") (pinfunction "P$1_X") (pintype "passive"))
      (node (ref "C1") (pin "2") (pinfunction "2_2") (pintype "passive"))
      (node (ref "C10") (pin "2") (pinfunction "2_2") (pintype "passive"))
      (node (ref "C11") (pin "2") (pinfunction "2_2") (pintype "passive"))
      (node (ref "C12") (pin "2") (pinfunction "2_2") (pintype "passive"))
      (node (ref "C13") (pin "2") (pinfunction "2_2") (pintype "passive"))
      (node (ref "C14") (pin "2") (pinfunction "2_2") (pintype "passive"))
      (node (ref "C16") (pin "2") (pinfunction "2_2") (pintype "passive"))
      (node (ref "C17") (pin "2") (pinfunction "2_2") (pintype "passive"))
      (node (ref "C18") (pin "2") (pinfunction "2_2") (pintype "passive"))
      (node (ref "C19") (pin "2") (pinfunction "2_2") (pintype "passive"))
      (node (ref "C2") (pin "2") (pinfunction "2_2") (pintype "passive"))
      (node (ref "C20") (pin "2") (pinfunction "2_2") (pintype "passive"))
      (node (ref "C21") (pin "2") (pinfunction "2_2") (pintype "passive"))
      (node (ref "C22") (pin "2") (pinfunction "2_2") (pintype "passive"))
      (node (ref "C23") (pin "2") (pinfunction "2_2") (pintype "passive"))
      (node (ref "C24") (pin "2") (pinfunction "2_2") (pintype "passive"))
      (node (ref "C25") (pin "2") (pinfunction "2_2") (pintype "passive"))
      (node (ref "C26") (pin "2") (pinfunction "2_2") (pintype "passive"))
      (node (ref "C27") (pin "2") (pinfunction "2_2") (pintype "passive"))
      (node (ref "C28") (pin "2") (pinfunction "2_2") (pintype "passive"))
      (node (ref "C29") (pin "2") (pinfunction "2_2") (pintype "passive"))
      (node (ref "C3") (pin "1") (pinfunction "1_1") (pintype "passive"))
      (node (ref "C30") (pin "2") (pinfunction "2_2") (pintype "passive"))
      (node (ref "C31") (pin "1") (pinfunction "1_1") (pintype "passive"))
      (node (ref "C4") (pin "1") (pinfunction "1_1") (pintype "passive"))
      (node (ref "C5") (pin "2") (pinfunction "2_2") (pintype "passive"))
      (node (ref "C6") (pin "2") (pinfunction "2_2") (pintype "passive"))
      (node (ref "C7") (pin "2") (pinfunction "2_2") (pintype "passive"))
      (node (ref "C8") (pin "2") (pinfunction "2_2") (pintype "passive"))
      (node (ref "C9") (pin "2") (pinfunction "2_2") (pintype "passive"))
      (node (ref "D2") (pin "A") (pinfunction "A_A") (pintype "passive"))
      (node (ref "DL3") (pin "C") (pinfunction "C_C") (pintype "passive"))
      (node (ref "GND") (pin "X") (pinfunction "P$1_X") (pintype "passive"))
      (node (ref "J1") (pin "5") (pinfunction "5_5") (pintype "passive"))
      (node (ref "J2") (pin "5") (pinfunction "5_5") (pintype "passive"))
      (node (ref "J4") (pin "5") (pinfunction "5_5") (pintype "passive"))
      (node (ref "J4") (pin "SH1") (pinfunction "SH_SH1") (pintype "passive"))
      (node (ref "J4") (pin "SH2") (pinfunction "SH_SH2") (pintype "passive"))
      (node (ref "J5") (pin "11") (pinfunction "11_11") (pintype "passive"))
      (node (ref "J7") (pin "2") (pinfunction "2_2") (pintype "passive"))
      (node (ref "J7") (pin "3") (pinfunction "SH_3") (pintype "passive"))
      (node (ref "J7") (pin "4") (pinfunction "SH_4") (pintype "passive"))
      (node (ref "J8") (pin "GND1") (pinfunction "GND_GND1") (pintype "bidirectional"))
      (node (ref "J8") (pin "GND2") (pinfunction "GND_GND2") (pintype "bidirectional"))
      (node (ref "M1") (pin "25") (pinfunction "GND_25") (pintype "bidirectional"))
      (node (ref "M1") (pin "27") (pinfunction "GND_27") (pintype "bidirectional"))
      (node (ref "M1") (pin "3") (pinfunction "GND_3") (pintype "bidirectional"))
      (node (ref "M1") (pin "38") (pinfunction "PB7/LPTIM1_IN2_38") (pintype "bidirectional"))
      (node (ref "M1") (pin "44") (pinfunction "GND_44") (pintype "bidirectional"))
      (node (ref "M1") (pin "49") (pinfunction "GND_49") (pintype "bidirectional"))
      (node (ref "M1") (pin "50") (pinfunction "GND_50") (pintype "bidirectional"))
      (node (ref "M1") (pin "51") (pinfunction "GND_51") (pintype "bidirectional"))
      (node (ref "M1") (pin "52") (pinfunction "GND_52") (pintype "bidirectional"))
      (node (ref "M1") (pin "53") (pinfunction "GND_53") (pintype "bidirectional"))
      (node (ref "M1") (pin "54") (pinfunction "GND_54") (pintype "bidirectional"))
      (node (ref "M1") (pin "55") (pinfunction "GND_55") (pintype "bidirectional"))
      (node (ref "M1") (pin "56") (pinfunction "GND_56") (pintype "bidirectional"))
      (node (ref "M1") (pin "57") (pinfunction "GND_57") (pintype "bidirectional"))
      (node (ref "M1") (pin "7") (pinfunction "GND_7") (pintype "bidirectional"))
      (node (ref "PB1") (pin "1") (pinfunction "3_1") (pintype "power_in"))
      (node (ref "PB1") (pin "2") (pinfunction "3_2") (pintype "power_in"))
      (node (ref "PB1") (pin "3") (pinfunction "3_3") (pintype "power_in"))
      (node (ref "PB1") (pin "4") (pinfunction "3_4") (pintype "power_in"))
      (node (ref "PB1") (pin "5") (pinfunction "1_5") (pintype "passive"))
      (node (ref "Q1") (pin "S") (pinfunction "S_S") (pintype "passive"))
      (node (ref "Q3") (pin "S") (pinfunction "S_S") (pintype "passive"))
      (node (ref "R1") (pin "1") (pinfunction "1_1") (pintype "passive"))
      (node (ref "R16") (pin "1") (pinfunction "1_1") (pintype "passive"))
      (node (ref "R19") (pin "1") (pinfunction "1_1") (pintype "passive"))
      (node (ref "R25") (pin "1") (pinfunction "1_1") (pintype "passive"))
      (node (ref "R28") (pin "2") (pinfunction "2_2") (pintype "passive"))
      (node (ref "R29") (pin "1") (pinfunction "1_1") (pintype "passive"))
      (node (ref "R7") (pin "1") (pinfunction "1_1") (pintype "passive"))
      (node (ref "U1") (pin "18") (pinfunction "GND_18") (pintype "power_in"))
      (node (ref "U1") (pin "35") (pinfunction "GND_35") (pintype "power_in"))
      (node (ref "U1") (pin "42") (pinfunction "GND_42") (pintype "power_in"))
      (node (ref "U1") (pin "49") (pinfunction "EP_49") (pintype "passive"))
      (node (ref "U1") (pin "5") (pinfunction "GNDANA_5") (pintype "power_in"))
      (node (ref "U2") (pin "4") (pinfunction "GND_4") (pintype "power_in"))
      (node (ref "U2") (pin "9") (pinfunction "EP_9") (pintype "passive"))
      (node (ref "U4") (pin "4") (pinfunction "GND_4") (pintype "power_in"))
      (node (ref "U4") (pin "9") (pinfunction "EP_9") (pintype "passive"))
      (node (ref "U5") (pin "17") (pinfunction "PGND_17") (pintype "bidirectional"))
      (node (ref "U5") (pin "18") (pinfunction "PGND_18") (pintype "bidirectional"))
      (node (ref "U5") (pin "25") (pinfunction "TH_25") (pintype "bidirectional"))
      (node (ref "U6") (pin "2") (pinfunction "GND/ADJ_2") (pintype "power_in"))
    )
    (net (code "5") (name "Net-(C1-Pad1)") (class "Default")
      (node (ref "C1") (pin "1") (pinfunction "1_1") (pintype "passive"))
      (node (ref "D1") (pin "1") (pinfunction "1_1") (pintype "passive"))
      (node (ref "J1") (pin "10") (pinfunction "SH_10") (pintype "passive"))
      (node (ref "J1") (pin "11") (pinfunction "SH_11") (pintype "passive"))
      (node (ref "J1") (pin "6") (pinfunction "SH_6") (pintype "passive"))
      (node (ref "J1") (pin "7") (pinfunction "SH_7") (pintype "passive"))
      (node (ref "J1") (pin "8") (pinfunction "SH_8") (pintype "passive"))
      (node (ref "J1") (pin "9") (pinfunction "SH_9") (pintype "passive"))
      (node (ref "R1") (pin "2") (pinfunction "2_2") (pintype "passive"))
    )
    (net (code "6") (name "Net-(C14-Pad1)") (class "Default")
      (node (ref "C14") (pin "1") (pinfunction "1_1") (pintype "passive"))
      (node (ref "Q2") (pin "K") (pinfunction "C_K") (pintype "passive"))
      (node (ref "Q2") (pin "K2") (pinfunction "C_K2") (pintype "passive"))
      (node (ref "Q2") (pin "S") (pinfunction "S_S") (pintype "passive"))
      (node (ref "R27") (pin "2") (pinfunction "2_2") (pintype "passive"))
      (node (ref "U5") (pin "1") (pinfunction "VBUS_1") (pintype "bidirectional"))
      (node (ref "U5") (pin "24") (pinfunction "VBUS_24") (pintype "bidirectional"))
    )
    (net (code "7") (name "Net-(C15-Pad2)") (class "Default")
      (node (ref "C15") (pin "2") (pinfunction "2_2") (pintype "passive"))
      (node (ref "L2") (pin "1") (pinfunction "1_1") (pintype "passive"))
      (node (ref "U5") (pin "19") (pinfunction "SW_19") (pintype "bidirectional"))
      (node (ref "U5") (pin "20") (pinfunction "SW_20") (pintype "bidirectional"))
    )
    (net (code "8") (name "Net-(C30-Pad1)") (class "Default")
      (node (ref "C30") (pin "1") (pinfunction "1_1") (pintype "passive"))
      (node (ref "J8") (pin "SIG") (pinfunction "SIG_SIG") (pintype "bidirectional"))
      (node (ref "R10") (pin "2") (pinfunction "2_2") (pintype "passive"))
    )
    (net (code "9") (name "Net-(DL1-PadA)") (class "Default")
      (node (ref "DL1") (pin "A") (pinfunction "A_A") (pintype "passive"))
      (node (ref "R15") (pin "2") (pinfunction "2_2") (pintype "passive"))
    )
    (net (code "10") (name "Net-(DL1-PadC)") (class "Default")
      (node (ref "DL1") (pin "C") (pinfunction "C_C") (pintype "passive"))
      (node (ref "Q1") (pin "D") (pinfunction "D_D") (pintype "passive"))
    )
    (net (code "11") (name "Net-(DL2-PadA)") (class "Default")
      (node (ref "DL2") (pin "A") (pinfunction "A_A") (pintype "passive"))
      (node (ref "R23") (pin "1") (pinfunction "1_1") (pintype "passive"))
    )
    (net (code "12") (name "Net-(DL3-PadA)") (class "Default")
      (node (ref "DL3") (pin "A") (pinfunction "A_A") (pintype "passive"))
      (node (ref "R27") (pin "1") (pinfunction "1_1") (pintype "passive"))
    )
    (net (code "13") (name "Net-(DM-P$1)") (class "Default")
      (node (ref "DM") (pin "X") (pinfunction "P$1_X") (pintype "passive"))
      (node (ref "M1") (pin "2") (pinfunction "PA11/USB-_2") (pintype "bidirectional"))
    )
    (net (code "14") (name "Net-(DP-P$1)") (class "Default")
      (node (ref "DP") (pin "X") (pinfunction "P$1_X") (pintype "passive"))
      (node (ref "M1") (pin "1") (pinfunction "PA12/USB+_1") (pintype "bidirectional"))
    )
    (net (code "15") (name "Net-(F1-Pad1)") (class "Default")
      (node (ref "F1") (pin "1") (pinfunction "1_1") (pintype "passive"))
      (node (ref "J5") (pin "14") (pinfunction "14_14") (pintype "passive"))
    )
    (net (code "16") (name "Net-(F2-Pad1)") (class "Default")
      (node (ref "F2") (pin "1") (pinfunction "1_1") (pintype "passive"))
      (node (ref "J7") (pin "1") (pinfunction "1_1") (pintype "passive"))
    )
    (net (code "17") (name "Net-(J2-Pad3)") (class "Default")
      (node (ref "J2") (pin "3") (pinfunction "3_3") (pintype "passive"))
      (node (ref "R2") (pin "1") (pinfunction "1_1") (pintype "passive"))
    )
    (net (code "18") (name "Net-(M1-ANT)") (class "Default")
      (node (ref "C29") (pin "1") (pinfunction "1_1") (pintype "passive"))
      (node (ref "M1") (pin "26") (pinfunction "ANT_26") (pintype "bidirectional"))
      (node (ref "R10") (pin "1") (pinfunction "1_1") (pintype "passive"))
    )
    (net (code "19") (name "Net-(M1-DIO4)") (class "Default")
      (node (ref "M1") (pin "10") (pinfunction "DIO4_10") (pintype "bidirectional"))
      (node (ref "R18") (pin "1") (pinfunction "1_1") (pintype "passive"))
    )
    (net (code "20") (name "Net-(M1-PA5{slash}ADC5{slash}DAC2)") (class "Default")
      (node (ref "M1") (pin "21") (pinfunction "PA5/ADC5/DAC2_21") (pintype "bidirectional"))
      (node (ref "R18") (pin "2") (pinfunction "2_2") (pintype "passive"))
    )
    (net (code "21") (name "Net-(M1-PA13{slash}SWDIO)") (class "Default")
      (node (ref "M1") (pin "41") (pinfunction "PA13/SWDIO_41") (pintype "bidirectional"))
      (node (ref "ST_SWDIO") (pin "X") (pinfunction "P$1_X") (pintype "passive"))
    )
    (net (code "22") (name "Net-(M1-PA14{slash}SWCLK)") (class "Default")
      (node (ref "M1") (pin "42") (pinfunction "PA14/SWCLK_42") (pintype "bidirectional"))
      (node (ref "ST_SWCLK") (pin "X") (pinfunction "P$1_X") (pintype "passive"))
    )
    (net (code "23") (name "Net-(M1-PB6{slash}LPTIM1_ETR)") (class "Default")
      (node (ref "M1") (pin "39") (pinfunction "PB6/LPTIM1_ETR_39") (pintype "bidirectional"))
      (node (ref "M1") (pin "48") (pinfunction "VDD_TCX0_48") (pintype "bidirectional"))
    )
    (net (code "24") (name "Net-(M1-PB14{slash}MISO)") (class "Default")
      (node (ref "M1") (pin "15") (pinfunction "PB14/MISO_15") (pintype "bidirectional"))
      (node (ref "R20") (pin "1") (pinfunction "1_1") (pintype "passive"))
    )
    (net (code "25") (name "Net-(M1-PH0-OSC_IN)") (class "Default")
      (node (ref "M1") (pin "46") (pinfunction "PH0-OSC_IN_46") (pintype "bidirectional"))
      (node (ref "R17") (pin "1") (pinfunction "1_1") (pintype "passive"))
    )
    (net (code "26") (name "Net-(M1-TCX0_OUT)") (class "Default")
      (node (ref "M1") (pin "47") (pinfunction "TCX0_OUT_47") (pintype "bidirectional"))
      (node (ref "R17") (pin "2") (pinfunction "2_2") (pintype "passive"))
    )
    (net (code "27") (name "Net-(M1-VBUS)") (class "Default")
      (node (ref "M1") (pin "4") (pinfunction "VBUS_4") (pintype "bidirectional"))
      (node (ref "R9") (pin "1") (pinfunction "1_1") (pintype "passive"))
    )
    (net (code "28") (name "Net-(PB1-2)") (class "Default")
      (node (ref "PB1") (pin "6") (pinfunction "2_6") (pintype "passive"))
      (node (ref "R3") (pin "1") (pinfunction "1_1") (pintype "passive"))
    )
    (net (code "29") (name "Net-(U1B-VDDANA)") (class "Default")
      (node (ref "C23") (pin "1") (pinfunction "1_1") (pintype "passive"))
      (node (ref "C27") (pin "1") (pinfunction "1_1") (pintype "passive"))
      (node (ref "L3") (pin "2") (pinfunction "2_2") (pintype "passive"))
      (node (ref "U1") (pin "6") (pinfunction "VDDANA_6") (pintype "power_in"))
    )
    (net (code "30") (name "Net-(U1B-VDDCORE)") (class "Default")
      (node (ref "C25") (pin "1") (pinfunction "1_1") (pintype "passive"))
      (node (ref "U1") (pin "43") (pinfunction "VDDCORE_43") (pintype "power_in"))
    )
    (net (code "31") (name "Net-(U5-BTST)") (class "Default")
      (node (ref "C15") (pin "1") (pinfunction "1_1") (pintype "passive"))
      (node (ref "U5") (pin "21") (pinfunction "BTST_21") (pintype "bidirectional"))
    )
    (net (code "32") (name "Net-(U5-CE)") (class "Default")
      (node (ref "R25") (pin "2") (pinfunction "2_2") (pintype "passive"))
      (node (ref "U5") (pin "9") (pinfunction "CE_9") (pintype "bidirectional"))
    )
    (net (code "33") (name "Net-(U5-ILIM)") (class "Default")
      (node (ref "R28") (pin "1") (pinfunction "1_1") (pintype "passive"))
      (node (ref "U5") (pin "10") (pinfunction "ILIM_10") (pintype "bidirectional"))
    )
    (net (code "34") (name "Net-(U5-INT)") (class "Default")
      (node (ref "R24") (pin "2") (pinfunction "2_2") (pintype "passive"))
      (node (ref "U5") (pin "7") (pinfunction "INT_7") (pintype "bidirectional"))
    )
    (net (code "35") (name "Net-(U5-OTG)") (class "Default")
      (node (ref "Q3") (pin "D") (pinfunction "D_D") (pintype "passive"))
      (node (ref "R26") (pin "2") (pinfunction "2_2") (pintype "passive"))
      (node (ref "U5") (pin "8") (pinfunction "OTG_8") (pintype "bidirectional"))
    )
    (net (code "36") (name "Net-(U5-PMID)") (class "Default")
      (node (ref "C12") (pin "1") (pinfunction "1_1") (pintype "passive"))
      (node (ref "C13") (pin "1") (pinfunction "1_1") (pintype "passive"))
      (node (ref "D3") (pin "A") (pinfunction "A_A") (pintype "passive"))
      (node (ref "U5") (pin "23") (pinfunction "PMID_23") (pintype "bidirectional"))
    )
    (net (code "37") (name "Net-(U5-REGN)") (class "Default")
      (node (ref "C16") (pin "1") (pinfunction "1_1") (pintype "passive"))
      (node (ref "R30") (pin "1") (pinfunction "1_1") (pintype "passive"))
      (node (ref "U5") (pin "22") (pinfunction "REGN_22") (pintype "bidirectional"))
    )
    (net (code "38") (name "Net-(U5-STAT)") (class "Default")
      (node (ref "DL2") (pin "C") (pinfunction "C_C") (pintype "passive"))
      (node (ref "U5") (pin "4") (pinfunction "STAT_4") (pintype "bidirectional"))
    )
    (net (code "39") (name "Net-(U5-TS1)") (class "Default")
      (node (ref "R29") (pin "2") (pinfunction "2_2") (pintype "passive"))
      (node (ref "R30") (pin "2") (pinfunction "2_2") (pintype "passive"))
      (node (ref "U5") (pin "11") (pinfunction "TS1_11") (pintype "bidirectional"))
      (node (ref "U5") (pin "12") (pinfunction "TS2_12") (pintype "bidirectional"))
    )
    (net (code "40") (name "Net-(U6-OUT)") (class "Default")
      (node (ref "SJ1") (pin "1") (pinfunction "1_1") (pintype "passive"))
      (node (ref "U6") (pin "5") (pinfunction "OUT_5") (pintype "power_in"))
    )
    (net (code "41") (name "PA00_XIN32") (class "Default")
      (node (ref "C3") (pin "2") (pinfunction "2_2") (pintype "passive"))
      (node (ref "U1") (pin "1") (pinfunction "PA00/XIN32_1") (pintype "bidirectional"))
      (node (ref "Y1") (pin "2") (pinfunction "2_2") (pintype "passive"))
    )
    (net (code "42") (name "PA01_XOUT32") (class "Default")
      (node (ref "C4") (pin "2") (pinfunction "2_2") (pintype "passive"))
      (node (ref "U1") (pin "2") (pinfunction "PA01/XOUT32_2") (pintype "bidirectional"))
      (node (ref "Y1") (pin "1") (pinfunction "1_1") (pintype "passive"))
    )
    (net (code "43") (name "PA02_AIN0") (class "Default")
      (node (ref "J3") (pin "2") (pinfunction "2_2") (pintype "passive"))
      (node (ref "U1") (pin "3") (pinfunction "PA02_3") (pintype "bidirectional"))
    )
    (net (code "44") (name "PA03_VREFA") (class "Default")
      (node (ref "C5") (pin "1") (pinfunction "1_1") (pintype "passive"))
      (node (ref "C7") (pin "1") (pinfunction "1_1") (pintype "passive"))
      (node (ref "J3") (pin "1") (pinfunction "1_1") (pintype "passive"))
      (node (ref "U1") (pin "4") (pinfunction "PA03_4") (pintype "bidirectional"))
    )
    (net (code "45") (name "PA04_AIN4") (class "Default")
      (node (ref "J3") (pin "5") (pinfunction "5_5") (pintype "passive"))
      (node (ref "U1") (pin "9") (pinfunction "PA04_9") (pintype "bidirectional"))
    )
    (net (code "46") (name "PA05_AIN5") (class "Default")
      (node (ref "J3") (pin "6") (pinfunction "6_6") (pintype "passive"))
      (node (ref "U1") (pin "10") (pinfunction "PA05_10") (pintype "bidirectional"))
    )
    (net (code "47") (name "PA06_AIN6") (class "Default")
      (node (ref "J3") (pin "7") (pinfunction "7_7") (pintype "passive"))
      (node (ref "U1") (pin "11") (pinfunction "PA06_11") (pintype "bidirectional"))
    )
    (net (code "48") (name "PA07_AIN7") (class "Default")
      (node (ref "J3") (pin "8") (pinfunction "8_8") (pintype "passive"))
      (node (ref "U1") (pin "12") (pinfunction "PA07_12") (pintype "bidirectional"))
    )
    (net (code "49") (name "PA08_S0_I2C_SDA") (class "Default")
      (node (ref "ESDA") (pin "X") (pinfunction "P$1_X") (pintype "passive"))
      (node (ref "J4") (pin "4") (pinfunction "4_4") (pintype "passive"))
      (node (ref "J5") (pin "6") (pinfunction "6_6") (pintype "passive"))
      (node (ref "M1") (pin "36") (pinfunction "PB9/SDA1_36") (pintype "bidirectional"))
      (node (ref "R14") (pin "1") (pinfunction "1_1") (pintype "passive"))
      (node (ref "U1") (pin "13") (pinfunction "PA08_13") (pintype "bidirectional"))
      (node (ref "U4") (pin "5") (pinfunction "SDA_5") (pintype "bidirectional"))
      (node (ref "U5") (pin "6") (pinfunction "SDA_6") (pintype "bidirectional"))
    )
    (net (code "50") (name "PA09_S0_I2C_SCL") (class "Default")
      (node (ref "ESCL") (pin "X") (pinfunction "P$1_X") (pintype "passive"))
      (node (ref "J4") (pin "3") (pinfunction "3_3") (pintype "passive"))
      (node (ref "J5") (pin "7") (pinfunction "7_7") (pintype "passive"))
      (node (ref "M1") (pin "35") (pinfunction "PB8/SCL1_35") (pintype "bidirectional"))
      (node (ref "R13") (pin "1") (pinfunction "1_1") (pintype "passive"))
      (node (ref "U1") (pin "14") (pinfunction "PA09_14") (pintype "bidirectional"))
      (node (ref "U4") (pin "6") (pinfunction "SCL_6") (pintype "input"))
      (node (ref "U5") (pin "5") (pinfunction "SCL_5") (pintype "bidirectional"))
    )
    (net (code "51") (name "PA10_TCC0-W2") (class "Default")
      (node (ref "J3") (pin "11") (pinfunction "11_11") (pintype "passive"))
      (node (ref "U1") (pin "15") (pinfunction "PA10_15") (pintype "bidirectional"))
    )
    (net (code "52") (name "PA11_TCC0-W3") (class "Default")
      (node (ref "J3") (pin "12") (pinfunction "12_12") (pintype "passive"))
      (node (ref "U1") (pin "16") (pinfunction "PA11_16") (pintype "bidirectional"))
    )
    (net (code "53") (name "PA12_MOSI_TX") (class "Default")
      (node (ref "M1") (pin "14") (pinfunction "PB15/MOSI_14") (pintype "bidirectional"))
      (node (ref "M1") (pin "23") (pinfunction "PA3/ADC3_23") (pintype "bidirectional"))
      (node (ref "U1") (pin "21") (pinfunction "PA12_21") (pintype "bidirectional"))
      (node (ref "U2") (pin "5") (pinfunction "DI_5") (pintype "input"))
    )
    (net (code "54") (name "PA13_SCK") (class "Default")
      (node (ref "M1") (pin "16") (pinfunction "PB13/SCK_16") (pintype "bidirectional"))
      (node (ref "U1") (pin "22") (pinfunction "PA13_22") (pintype "bidirectional"))
      (node (ref "U2") (pin "6") (pinfunction "CLK_6") (pintype "input"))
    )
    (net (code "55") (name "PA14_RF_SSN") (class "Default")
      (node (ref "M1") (pin "17") (pinfunction "PB12/SS_17") (pintype "bidirectional"))
      (node (ref "R12") (pin "1") (pinfunction "1_1") (pintype "passive"))
      (node (ref "U1") (pin "23") (pinfunction "PA14_23") (pintype "bidirectional"))
    )
    (net (code "56") (name "PA15_MISO_RX") (class "Default")
      (node (ref "M1") (pin "24") (pinfunction "PA2/ADC2_24") (pintype "bidirectional"))
      (node (ref "R20") (pin "2") (pinfunction "2_2") (pintype "passive"))
      (node (ref "U1") (pin "24") (pinfunction "PA15_24") (pintype "bidirectional"))
      (node (ref "U2") (pin "2") (pinfunction "DO_2") (pintype "tri_state"))
    )
    (net (code "57") (name "PA16_S1_MOSI") (class "Default")
      (node (ref "J5") (pin "3") (pinfunction "3_3") (pintype "passive"))
      (node (ref "U1") (pin "25") (pinfunction "PA16_25") (pintype "bidirectional"))
    )
    (net (code "58") (name "PA17_S1_SCK") (class "Default")
      (node (ref "J5") (pin "4") (pinfunction "4_4") (pintype "passive"))
      (node (ref "U1") (pin "26") (pinfunction "PA17_26") (pintype "bidirectional"))
    )
    (net (code "59") (name "PA18_OTG") (class "Default")
      (node (ref "J1") (pin "4") (pinfunction "4_4") (pintype "passive"))
      (node (ref "Q3") (pin "G") (pinfunction "G_G") (pintype "passive"))
      (node (ref "R21") (pin "2") (pinfunction "2_2") (pintype "passive"))
      (node (ref "U1") (pin "27") (pinfunction "PA18_27") (pintype "bidirectional"))
    )
    (net (code "60") (name "PA19_S1_MISO") (class "Default")
      (node (ref "J5") (pin "5") (pinfunction "5_5") (pintype "passive"))
      (node (ref "U1") (pin "28") (pinfunction "PA19_28") (pintype "bidirectional"))
    )
    (net (code "61") (name "PA20_TCC0-W6") (class "Default")
      (node (ref "J5") (pin "1") (pinfunction "1_1") (pintype "passive"))
      (node (ref "Q1") (pin "G") (pinfunction "G_G") (pintype "passive"))
      (node (ref "R16") (pin "2") (pinfunction "2_2") (pintype "passive"))
      (node (ref "U1") (pin "29") (pinfunction "PA20_29") (pintype "bidirectional"))
    )
    (net (code "62") (name "PA21_TCC0-W7") (class "Default")
      (node (ref "EWK") (pin "X") (pinfunction "P$1_X") (pintype "passive"))
      (node (ref "J4") (pin "2") (pinfunction "2_2") (pintype "passive"))
      (node (ref "J5") (pin "2") (pinfunction "2_2") (pintype "passive"))
      (node (ref "U1") (pin "30") (pinfunction "PA21_30") (pintype "bidirectional"))
    )
    (net (code "63") (name "PA22_TC4-W0") (class "Default")
      (node (ref "J3") (pin "9") (pinfunction "9_9") (pintype "passive"))
      (node (ref "U1") (pin "31") (pinfunction "PA22_31") (pintype "bidirectional"))
    )
    (net (code "64") (name "PA23_TC4-W1") (class "Default")
      (node (ref "J3") (pin "10") (pinfunction "10_10") (pintype "passive"))
      (node (ref "U1") (pin "32") (pinfunction "PA23_32") (pintype "bidirectional"))
    )
    (net (code "65") (name "PA27_RF_NRES") (class "Default")
      (node (ref "M1") (pin "34") (pinfunction "MCU_NRST_34") (pintype "bidirectional"))
      (node (ref "R11") (pin "1") (pinfunction "1_1") (pintype "passive"))
      (node (ref "ST_RST") (pin "X") (pinfunction "P$1_X") (pintype "passive"))
      (node (ref "U1") (pin "39") (pinfunction "PA27_39") (pintype "bidirectional"))
    )
    (net (code "66") (name "PA28_RF_IRQ") (class "Default")
      (node (ref "M1") (pin "22") (pinfunction "PA4/ADC4/DAC1_22") (pintype "bidirectional"))
      (node (ref "U1") (pin "41") (pinfunction "PA28_41") (pintype "bidirectional"))
    )
    (net (code "67") (name "PA30_SWCLK") (class "Default")
      (node (ref "J2") (pin "4") (pinfunction "4_4") (pintype "passive"))
      (node (ref "R4") (pin "1") (pinfunction "1_1") (pintype "passive"))
      (node (ref "U1") (pin "45") (pinfunction "PA30/SWCLK_45") (pintype "bidirectional"))
    )
    (net (code "68") (name "PA31_SWDIO") (class "Default")
      (node (ref "J2") (pin "2") (pinfunction "2_2") (pintype "passive"))
      (node (ref "U1") (pin "46") (pinfunction "PA31/SWDIO_46") (pintype "bidirectional"))
    )
    (net (code "69") (name "PB02_AIN10") (class "Default")
      (node (ref "J3") (pin "3") (pinfunction "3_3") (pintype "passive"))
      (node (ref "U1") (pin "47") (pinfunction "PB02_47") (pintype "bidirectional"))
    )
    (net (code "70") (name "PB03_AIN11") (class "Default")
      (node (ref "J3") (pin "4") (pinfunction "4_4") (pintype "passive"))
      (node (ref "U1") (pin "48") (pinfunction "PB03_48") (pintype "bidirectional"))
    )
    (net (code "71") (name "PB08_CS-FLASH") (class "Default")
      (node (ref "R8") (pin "1") (pinfunction "1_1") (pintype "passive"))
      (node (ref "U1") (pin "7") (pinfunction "PB08_7") (pintype "bidirectional"))
      (node (ref "U2") (pin "1") (pinfunction "/CS_1") (pintype "input"))
    )
    (net (code "72") (name "PB09_BOOT0") (class "Default")
      (node (ref "M1") (pin "43") (pinfunction "BOOT0_43") (pintype "bidirectional"))
      (node (ref "R7") (pin "2") (pinfunction "2_2") (pintype "passive"))
      (node (ref "ST_BOOT0") (pin "X") (pinfunction "P$1_X") (pintype "passive"))
      (node (ref "U1") (pin "8") (pinfunction "PB09_8") (pintype "bidirectional"))
    )
    (net (code "73") (name "PB10_TCC0-W4") (class "Default")
      (node (ref "J3") (pin "13") (pinfunction "13_13") (pintype "passive"))
      (node (ref "U1") (pin "19") (pinfunction "PB10_19") (pintype "bidirectional"))
    )
    (net (code "74") (name "PB11_TCC0-W5") (class "Default")
      (node (ref "J3") (pin "14") (pinfunction "14_14") (pintype "passive"))
      (node (ref "U1") (pin "20") (pinfunction "PB11_20") (pintype "bidirectional"))
    )
    (net (code "75") (name "PB22_S5_TX") (class "Default")
      (node (ref "J5") (pin "9") (pinfunction "9_9") (pintype "passive"))
      (node (ref "U1") (pin "37") (pinfunction "PB22_37") (pintype "bidirectional"))
    )
    (net (code "76") (name "PB23_S5_RX") (class "Default")
      (node (ref "J5") (pin "8") (pinfunction "8_8") (pintype "passive"))
      (node (ref "U1") (pin "38") (pinfunction "PB23_38") (pintype "bidirectional"))
    )
    (net (code "77") (name "RESET#") (class "Default")
      (node (ref "J5") (pin "10") (pinfunction "10_10") (pintype "passive"))
      (node (ref "R6") (pin "2") (pinfunction "2_2") (pintype "passive"))
    )
    (net (code "78") (name "RESETN") (class "Default")
      (node (ref "C2") (pin "1") (pinfunction "1_1") (pintype "passive"))
      (node (ref "R2") (pin "2") (pinfunction "2_2") (pintype "passive"))
      (node (ref "R3") (pin "2") (pinfunction "2_2") (pintype "passive"))
      (node (ref "R5") (pin "1") (pinfunction "1_1") (pintype "passive"))
      (node (ref "R6") (pin "1") (pinfunction "1_1") (pintype "passive"))
      (node (ref "U1") (pin "40") (pinfunction "RESETN_40") (pintype "bidirectional"))
    )
    (net (code "79") (name "USB_N") (class "Default")
      (node (ref "D-") (pin "X") (pinfunction "P$1_X") (pintype "passive"))
      (node (ref "D1") (pin "3") (pinfunction "3_3") (pintype "passive"))
      (node (ref "J1") (pin "2") (pinfunction "2_2") (pintype "passive"))
      (node (ref "U1") (pin "33") (pinfunction "PA24/USB_DM_33") (pintype "bidirectional"))
    )
    (net (code "80") (name "USB_P") (class "Default")
      (node (ref "D+") (pin "X") (pinfunction "P$1_X") (pintype "passive"))
      (node (ref "D1") (pin "2") (pinfunction "2_2") (pintype "passive"))
      (node (ref "J1") (pin "3") (pinfunction "3_3") (pintype "passive"))
      (node (ref "U1") (pin "34") (pinfunction "PA25/USB_DP_34") (pintype "bidirectional"))
    )
    (net (code "81") (name "VBATT") (class "Default")
      (node (ref "BATT+") (pin "X") (pinfunction "P$1_X") (pintype "passive"))
      (node (ref "D2") (pin "C") (pinfunction "C_C") (pintype "passive"))
      (node (ref "F2") (pin "2") (pinfunction "2_2") (pintype "passive"))
      (node (ref "U5") (pin "13") (pinfunction "BAT_13") (pintype "bidirectional"))
      (node (ref "U5") (pin "14") (pinfunction "BAT_14") (pintype "bidirectional"))
    )
    (net (code "82") (name "VIN") (class "Default")
      (node (ref "J5") (pin "13") (pinfunction "13_13") (pintype "passive"))
      (node (ref "Q2") (pin "A") (pinfunction "A_A") (pintype "passive"))
      (node (ref "Q2") (pin "G") (pinfunction "G_G") (pintype "passive"))
      (node (ref "R19") (pin "2") (pinfunction "2_2") (pintype "passive"))
    )
    (net (code "83") (name "unconnected-(J2-Pad6)") (class "Default")
      (node (ref "J2") (pin "6") (pinfunction "6_6") (pintype "passive"))
    )
    (net (code "84") (name "unconnected-(M1-CRF1-Pad28)") (class "Default")
      (node (ref "M1") (pin "28") (pinfunction "CRF1_28") (pintype "bidirectional"))
    )
    (net (code "85") (name "unconnected-(M1-CRF2-Pad30)") (class "Default")
      (node (ref "M1") (pin "30") (pinfunction "CRF2_30") (pintype "bidirectional"))
    )
    (net (code "86") (name "unconnected-(M1-CRF3-Pad29)") (class "Default")
      (node (ref "M1") (pin "29") (pinfunction "CRF3_29") (pintype "bidirectional"))
    )
    (net (code "87") (name "unconnected-(M1-DIO0-Pad13)") (class "Default")
      (node (ref "M1") (pin "13") (pinfunction "DIO0_13") (pintype "bidirectional"))
    )
    (net (code "88") (name "unconnected-(M1-DIO1-Pad12)") (class "Default")
      (node (ref "M1") (pin "12") (pinfunction "DIO1_12") (pintype "bidirectional"))
    )
    (net (code "89") (name "unconnected-(M1-DIO2-Pad8)") (class "Default")
      (node (ref "M1") (pin "8") (pinfunction "DIO2_8") (pintype "bidirectional"))
    )
    (net (code "90") (name "unconnected-(M1-DIO3-Pad9)") (class "Default")
      (node (ref "M1") (pin "9") (pinfunction "DIO3_9") (pintype "bidirectional"))
    )
    (net (code "91") (name "unconnected-(M1-DIO5-Pad11)") (class "Default")
      (node (ref "M1") (pin "11") (pinfunction "DIO5_11") (pintype "bidirectional"))
    )
    (net (code "92") (name "unconnected-(M1-P57{slash}LPTIM1_IN1-Pad40)") (class "Default")
      (node (ref "M1") (pin "40") (pinfunction "P57/LPTIM1_IN1_40") (pintype "bidirectional"))
    )
    (net (code "93") (name "unconnected-(M1-PA0{slash}WKUP-Pad33)") (class "Default")
      (node (ref "M1") (pin "33") (pinfunction "PA0/WKUP_33") (pintype "bidirectional"))
    )
    (net (code "94") (name "unconnected-(M1-PA8{slash}MCO-Pad20)") (class "Default")
      (node (ref "M1") (pin "20") (pinfunction "PA8/MCO_20") (pintype "bidirectional"))
    )
    (net (code "95") (name "unconnected-(M1-PA10{slash}RX1-Pad18)") (class "Default")
      (node (ref "M1") (pin "18") (pinfunction "PA10/RX1_18") (pintype "bidirectional"))
    )
    (net (code "96") (name "unconnected-(M1-PA11{slash}TX1-Pad19)") (class "Default")
      (node (ref "M1") (pin "19") (pinfunction "PA11/TX1_19") (pintype "bidirectional"))
    )
    (net (code "97") (name "unconnected-(M1-PB2{slash}LPTIM1_OUT-Pad37)") (class "Default")
      (node (ref "M1") (pin "37") (pinfunction "PB2/LPTIM1_OUT_37") (pintype "bidirectional"))
    )
    (net (code "98") (name "unconnected-(M1-PH1-OSC_OUT-Pad45)") (class "Default")
      (node (ref "M1") (pin "45") (pinfunction "PH1-OSC_OUT_45") (pintype "bidirectional"))
    )
    (net (code "99") (name "unconnected-(M1-STSAFE_RST-Pad31)") (class "Default")
      (node (ref "M1") (pin "31") (pinfunction "STSAFE_RST_31") (pintype "bidirectional"))
    )
    (net (code "100") (name "unconnected-(U4B-NC-Pad1)") (class "Default")
      (node (ref "U4") (pin "1") (pinfunction "NC_1") (pintype "bidirectional"))
    )
    (net (code "101") (name "unconnected-(U4B-NC-Pad2)") (class "Default")
      (node (ref "U4") (pin "2") (pinfunction "NC_2") (pintype "bidirectional"))
    )
    (net (code "102") (name "unconnected-(U4B-NC-Pad3)") (class "Default")
      (node (ref "U4") (pin "3") (pinfunction "NC_3") (pintype "bidirectional"))
    )
    (net (code "103") (name "unconnected-(U4B-NC-Pad7)") (class "Default")
      (node (ref "U4") (pin "7") (pinfunction "NC_7") (pintype "bidirectional"))
    )
    (net (code "104") (name "unconnected-(U5-D+-Pad2)") (class "Default")
      (node (ref "U5") (pin "2") (pinfunction "D+_2") (pintype "bidirectional"))
    )
    (net (code "105") (name "unconnected-(U5-D--Pad3)") (class "Default")
      (node (ref "U5") (pin "3") (pinfunction "D-_3") (pintype "bidirectional"))
    )
  )
)
